# CMoy_Ampli.net
KiCad netlist of a schematic drawn in EAGLE
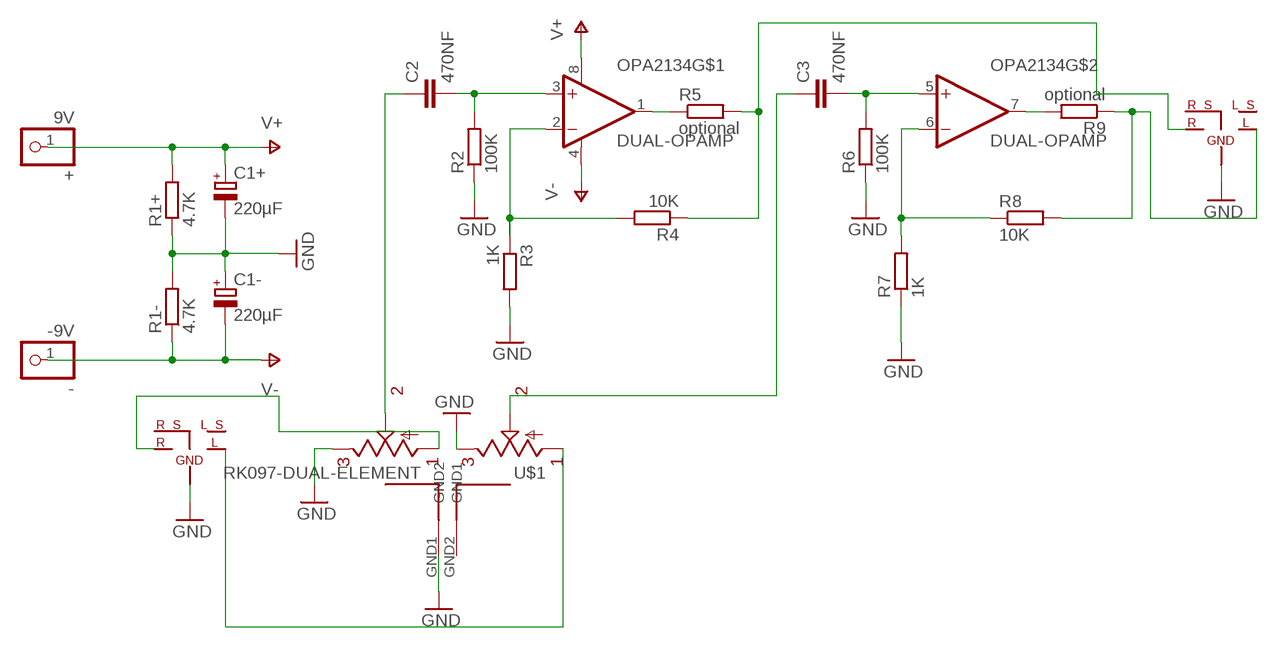
[diagram p0: schematic, sheet 1]

(export (version "E")
  (design (tool "Eeschema 10.0.6"))
  (components
    (comp (ref "+")
      (value "9V")
      (footprint "eagle-import:1X01")
      (libsource (lib "eagle-import") (part "PINHD-1X1"))
    )
    (comp (ref "-")
      (value "-9V")
      (footprint "eagle-import:1X01")
      (libsource (lib "eagle-import") (part "PINHD-1X1"))
    )
    (comp (ref "C1+")
      (value "220µF")
      (footprint "eagle-import:E3,5-8")
      (libsource (lib "eagle-import") (part "CPOL-EUE3.5-8"))
    )
    (comp (ref "C1-")
      (value "220µF")
      (footprint "eagle-import:E3,5-8")
      (libsource (lib "eagle-import") (part "CPOL-EUE3.5-8"))
    )
    (comp (ref "C2")
      (value "470NF")
      (footprint "eagle-import:C075-042X103")
      (libsource (lib "eagle-import") (part "C-EU075-042X103"))
    )
    (comp (ref "C3")
      (value "470NF")
      (footprint "eagle-import:C075-042X103")
      (libsource (lib "eagle-import") (part "C-EU075-042X103"))
    )
    (comp (ref "OPA2134")
      (value "DUAL-OPAMP")
      (footprint "eagle-import:DIP-8")
      (libsource (lib "eagle-import") (part "DUAL-OPAMP"))
    )
    (comp (ref "R1+")
      (value "4.7K")
      (footprint "eagle-import:0309V")
      (libsource (lib "eagle-import") (part "R-EU_0309/V"))
    )
    (comp (ref "R1-")
      (value "4.7K")
      (footprint "eagle-import:0309V")
      (libsource (lib "eagle-import") (part "R-EU_0309/V"))
    )
    (comp (ref "R2")
      (value "100K")
      (footprint "eagle-import:0309V")
      (libsource (lib "eagle-import") (part "R-EU_0309/V"))
    )
    (comp (ref "R3")
      (value "1K")
      (footprint "eagle-import:0309V")
      (libsource (lib "eagle-import") (part "R-EU_0309/V"))
    )
    (comp (ref "R4")
      (value "10K")
      (footprint "eagle-import:0309V")
      (libsource (lib "eagle-import") (part "R-EU_0309/V"))
    )
    (comp (ref "R5")
      (value "optional")
      (footprint "eagle-import:0309V")
      (libsource (lib "eagle-import") (part "R-EU_0309/V"))
    )
    (comp (ref "R6")
      (value "100K")
      (footprint "eagle-import:0309V")
      (libsource (lib "eagle-import") (part "R-EU_0309/V"))
    )
    (comp (ref "R7")
      (value "1K")
      (footprint "eagle-import:0309V")
      (libsource (lib "eagle-import") (part "R-EU_0309/V"))
    )
    (comp (ref "R8")
      (value "10K")
      (footprint "eagle-import:0309V")
      (libsource (lib "eagle-import") (part "R-EU_0309/V"))
    )
    (comp (ref "R9")
      (value "optional")
      (footprint "eagle-import:0309V")
      (libsource (lib "eagle-import") (part "R-EU_0309/V"))
    )
    (comp (ref "U$1")
      (value "RK097-DUAL-ELEMENT")
      (footprint "eagle-import:RK097-DUAL-ELEMENT")
      (libsource (lib "eagle-import") (part "RK097-DUAL-ELEMENT"))
    )
    (comp (ref "U$2")
      (value "EBS35")
      (footprint "eagle-import:EBS35")
      (libsource (lib "eagle-import") (part "EBS35"))
    )
    (comp (ref "U$3")
      (value "EBS35")
      (footprint "eagle-import:EBS35")
      (libsource (lib "eagle-import") (part "EBS35"))
    )
  )
  (nets
    (net (code "1") (name "GND") (class "Default")
      (node (ref "C1+") (pin "-") (pinfunction "-_-") (pintype "passive"))
      (node (ref "C1-") (pin "+") (pinfunction "+_+") (pintype "passive"))
      (node (ref "R1+") (pin "1") (pinfunction "1_1") (pintype "passive"))
      (node (ref "R1-") (pin "2") (pinfunction "2_2") (pintype "passive"))
      (node (ref "R2") (pin "1") (pinfunction "1_1") (pintype "passive"))
      (node (ref "R3") (pin "2") (pinfunction "2_2") (pintype "passive"))
      (node (ref "R6") (pin "1") (pinfunction "1_1") (pintype "passive"))
      (node (ref "R7") (pin "1") (pinfunction "1_1") (pintype "passive"))
      (node (ref "U$1") (pin "GND1") (pinfunction "GND2_GND1") (pintype "bidirectional"))
      (node (ref "U$1") (pin "IN1") (pinfunction "IN1_IN1") (pintype "passive"))
      (node (ref "U$1") (pin "IN2") (pinfunction "IN2_IN2") (pintype "passive"))
      (node (ref "U$2") (pin "GND") (pinfunction "GND_GND") (pintype "bidirectional"))
      (node (ref "U$3") (pin "GND") (pinfunction "GND_GND") (pintype "bidirectional"))
    )
    (net (code "2") (name "Net-(C2-Pad1)") (class "Default")
      (node (ref "C2") (pin "1") (pinfunction "1_1") (pintype "passive"))
      (node (ref "U$1") (pin "AMP1") (pinfunction "AMP1_AMP1") (pintype "passive"))
    )
    (net (code "3") (name "Net-(C3-Pad1)") (class "Default")
      (node (ref "C3") (pin "1") (pinfunction "1_1") (pintype "passive"))
      (node (ref "U$1") (pin "AMP2") (pinfunction "AMP2_AMP2") (pintype "passive"))
    )
    (net (code "4") (name "Net-(OPA2134A-+IN)") (class "Default")
      (node (ref "C2") (pin "2") (pinfunction "2_2") (pintype "passive"))
      (node (ref "OPA2134") (pin "3") (pinfunction "+IN_3") (pintype "input"))
      (node (ref "R2") (pin "2") (pinfunction "2_2") (pintype "passive"))
    )
    (net (code "5") (name "Net-(OPA2134A--IN)") (class "Default")
      (node (ref "OPA2134") (pin "2") (pinfunction "-IN_2") (pintype "input"))
      (node (ref "R3") (pin "1") (pinfunction "1_1") (pintype "passive"))
      (node (ref "R4") (pin "2") (pinfunction "2_2") (pintype "passive"))
    )
    (net (code "6") (name "Net-(OPA2134A-OUT)") (class "Default")
      (node (ref "OPA2134") (pin "1") (pinfunction "OUT_1") (pintype "output"))
      (node (ref "R5") (pin "1") (pinfunction "1_1") (pintype "passive"))
    )
    (net (code "7") (name "Net-(OPA2134B-+IN)") (class "Default")
      (node (ref "C3") (pin "2") (pinfunction "2_2") (pintype "passive"))
      (node (ref "OPA2134") (pin "5") (pinfunction "+IN_5") (pintype "input"))
      (node (ref "R6") (pin "2") (pinfunction "2_2") (pintype "passive"))
    )
    (net (code "8") (name "Net-(OPA2134B--IN)") (class "Default")
      (node (ref "OPA2134") (pin "6") (pinfunction "-IN_6") (pintype "input"))
      (node (ref "R7") (pin "2") (pinfunction "2_2") (pintype "passive"))
      (node (ref "R8") (pin "1") (pinfunction "1_1") (pintype "passive"))
    )
    (net (code "9") (name "Net-(OPA2134B-OUT)") (class "Default")
      (node (ref "OPA2134") (pin "7") (pinfunction "OUT_7") (pintype "output"))
      (node (ref "R9") (pin "2") (pinfunction "2_2") (pintype "passive"))
    )
    (net (code "10") (name "Net-(R4-Pad1)") (class "Default")
      (node (ref "R4") (pin "1") (pinfunction "1_1") (pintype "passive"))
      (node (ref "R5") (pin "2") (pinfunction "2_2") (pintype "passive"))
      (node (ref "U$3") (pin "R") (pinfunction "R_R") (pintype "bidirectional"))
    )
    (net (code "11") (name "Net-(R8-Pad2)") (class "Default")
      (node (ref "R8") (pin "2") (pinfunction "2_2") (pintype "passive"))
      (node (ref "R9") (pin "1") (pinfunction "1_1") (pintype "passive"))
      (node (ref "U$3") (pin "L") (pinfunction "L_L") (pintype "bidirectional"))
    )
    (net (code "12") (name "Net-(U$1-PadGND11)") (class "Default")
      (node (ref "U$1") (pin "GND11") (pinfunction "GND11_GND11") (pintype "passive"))
      (node (ref "U$2") (pin "R") (pinfunction "R_R") (pintype "bidirectional"))
    )
    (net (code "13") (name "Net-(U$1-PadGND12)") (class "Default")
      (node (ref "U$1") (pin "GND12") (pinfunction "GND12_GND12") (pintype "passive"))
      (node (ref "U$2") (pin "L") (pinfunction "L_L") (pintype "bidirectional"))
    )
    (net (code "14") (name "V+") (class "Default")
      (node (ref "+") (pin "1") (pinfunction "1_1") (pintype "passive"))
      (node (ref "C1+") (pin "+") (pinfunction "+_+") (pintype "passive"))
      (node (ref "OPA2134") (pin "8") (pinfunction "V+_8") (pintype "power_in"))
      (node (ref "R1+") (pin "2") (pinfunction "2_2") (pintype "passive"))
    )
    (net (code "15") (name "V-") (class "Default")
      (node (ref "-") (pin "1") (pinfunction "1_1") (pintype "passive"))
      (node (ref "C1-") (pin "-") (pinfunction "-_-") (pintype "passive"))
      (node (ref "OPA2134") (pin "4") (pinfunction "V-_4") (pintype "power_in"))
      (node (ref "R1-") (pin "1") (pinfunction "1_1") (pintype "passive"))
    )
    (net (code "16") (name "unconnected-(U$1-GND1-PadGND2)") (class "Default")
      (node (ref "U$1") (pin "GND2") (pinfunction "GND1_GND2") (pintype "bidirectional"))
    )
    (net (code "17") (name "unconnected-(U$2-L_S-PadL_SENS)") (class "Default")
      (node (ref "U$2") (pin "L_SENS") (pinfunction "L_S_L_SENS") (pintype "bidirectional"))
    )
    (net (code "18") (name "unconnected-(U$2-R_S-PadR_SENS)") (class "Default")
      (node (ref "U$2") (pin "R_SENS") (pinfunction "R_S_R_SENS") (pintype "bidirectional"))
    )
    (net (code "19") (name "unconnected-(U$3-L_S-PadL_SENS)") (class "Default")
      (node (ref "U$3") (pin "L_SENS") (pinfunction "L_S_L_SENS") (pintype "bidirectional"))
    )
    (net (code "20") (name "unconnected-(U$3-R_S-PadR_SENS)") (class "Default")
      (node (ref "U$3") (pin "R_SENS") (pinfunction "R_S_R_SENS") (pintype "bidirectional"))
    )
  )
)
